# LightSwitch.net
KiCad netlist of a schematic drawn in EAGLE
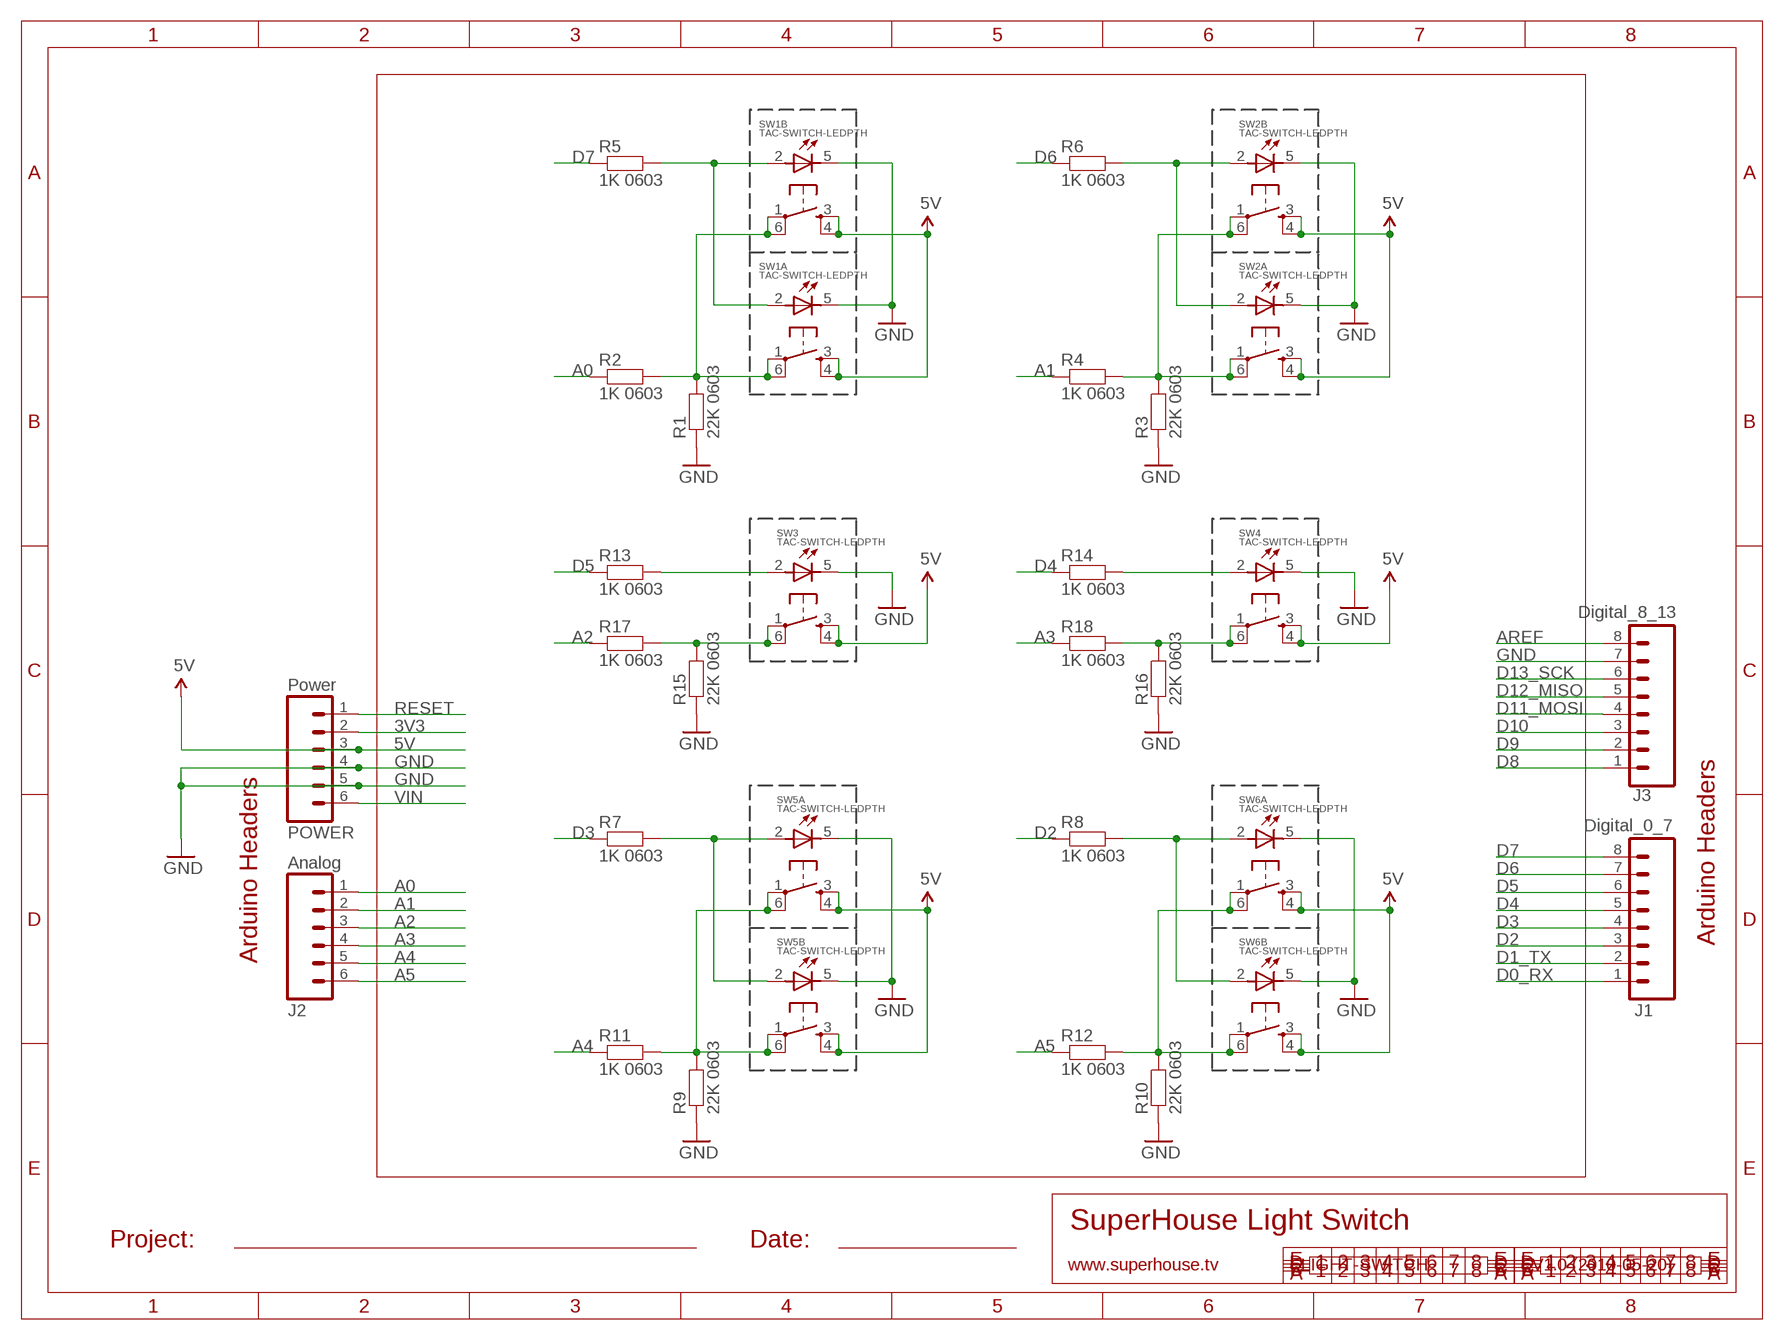
[diagram p0: schematic, sheet 1]

(export (version "E")
  (design (tool "Eeschema 10.0.6"))
  (components
    (comp (ref "J1")
      (value "Digital_0_7")
      (footprint "eagle-import:1X08")
      (libsource (lib "eagle-import") (part "M08"))
    )
    (comp (ref "J2")
      (value "Analog")
      (footprint "eagle-import:1X06")
      (libsource (lib "eagle-import") (part "M06SIP"))
    )
    (comp (ref "J3")
      (value "Digital_8_13")
      (footprint "eagle-import:1X08")
      (libsource (lib "eagle-import") (part "M08"))
    )
    (comp (ref "POWER")
      (value "Power")
      (footprint "eagle-import:1X06")
      (libsource (lib "eagle-import") (part "M06SIP"))
    )
    (comp (ref "R1")
      (value "22K 0603")
      (footprint "eagle-import:0603")
      (libsource (lib "eagle-import") (part "RESISTOR0603"))
    )
    (comp (ref "R2")
      (value "1K 0603")
      (footprint "eagle-import:0603")
      (libsource (lib "eagle-import") (part "RESISTOR0603"))
    )
    (comp (ref "R3")
      (value "22K 0603")
      (footprint "eagle-import:0603")
      (libsource (lib "eagle-import") (part "RESISTOR0603"))
    )
    (comp (ref "R4")
      (value "1K 0603")
      (footprint "eagle-import:0603")
      (libsource (lib "eagle-import") (part "RESISTOR0603"))
    )
    (comp (ref "R5")
      (value "1K 0603")
      (footprint "eagle-import:0603")
      (libsource (lib "eagle-import") (part "RESISTOR0603"))
    )
    (comp (ref "R6")
      (value "1K 0603")
      (footprint "eagle-import:0603")
      (libsource (lib "eagle-import") (part "RESISTOR0603"))
    )
    (comp (ref "R7")
      (value "1K 0603")
      (footprint "eagle-import:0603")
      (libsource (lib "eagle-import") (part "RESISTOR0603"))
    )
    (comp (ref "R8")
      (value "1K 0603")
      (footprint "eagle-import:0603")
      (libsource (lib "eagle-import") (part "RESISTOR0603"))
    )
    (comp (ref "R9")
      (value "22K 0603")
      (footprint "eagle-import:0603")
      (libsource (lib "eagle-import") (part "RESISTOR0603"))
    )
    (comp (ref "R10")
      (value "22K 0603")
      (footprint "eagle-import:0603")
      (libsource (lib "eagle-import") (part "RESISTOR0603"))
    )
    (comp (ref "R11")
      (value "1K 0603")
      (footprint "eagle-import:0603")
      (libsource (lib "eagle-import") (part "RESISTOR0603"))
    )
    (comp (ref "R12")
      (value "1K 0603")
      (footprint "eagle-import:0603")
      (libsource (lib "eagle-import") (part "RESISTOR0603"))
    )
    (comp (ref "R13")
      (value "1K 0603")
      (footprint "eagle-import:0603")
      (libsource (lib "eagle-import") (part "RESISTOR0603"))
    )
    (comp (ref "R14")
      (value "1K 0603")
      (footprint "eagle-import:0603")
      (libsource (lib "eagle-import") (part "RESISTOR0603"))
    )
    (comp (ref "R15")
      (value "22K 0603")
      (footprint "eagle-import:0603")
      (libsource (lib "eagle-import") (part "RESISTOR0603"))
    )
    (comp (ref "R16")
      (value "22K 0603")
      (footprint "eagle-import:0603")
      (libsource (lib "eagle-import") (part "RESISTOR0603"))
    )
    (comp (ref "R17")
      (value "1K 0603")
      (footprint "eagle-import:0603")
      (libsource (lib "eagle-import") (part "RESISTOR0603"))
    )
    (comp (ref "R18")
      (value "1K 0603")
      (footprint "eagle-import:0603")
      (libsource (lib "eagle-import") (part "RESISTOR0603"))
    )
    (comp (ref "SW1A")
      (value "TAC-SWITCH-LEDPTH")
      (footprint "eagle-import:TACTILE-LED")
      (libsource (lib "eagle-import") (part "TAC-SWITCH-LEDPTH"))
    )
    (comp (ref "SW1B")
      (value "TAC-SWITCH-LEDPTH")
      (footprint "eagle-import:TACTILE-LED")
      (libsource (lib "eagle-import") (part "TAC-SWITCH-LEDPTH"))
    )
    (comp (ref "SW2A")
      (value "TAC-SWITCH-LEDPTH")
      (footprint "eagle-import:TACTILE-LED")
      (libsource (lib "eagle-import") (part "TAC-SWITCH-LEDPTH"))
    )
    (comp (ref "SW2B")
      (value "TAC-SWITCH-LEDPTH")
      (footprint "eagle-import:TACTILE-LED")
      (libsource (lib "eagle-import") (part "TAC-SWITCH-LEDPTH"))
    )
    (comp (ref "SW3")
      (value "TAC-SWITCH-LEDPTH")
      (footprint "eagle-import:TACTILE-LED")
      (libsource (lib "eagle-import") (part "TAC-SWITCH-LEDPTH"))
    )
    (comp (ref "SW4")
      (value "TAC-SWITCH-LEDPTH")
      (footprint "eagle-import:TACTILE-LED")
      (libsource (lib "eagle-import") (part "TAC-SWITCH-LEDPTH"))
    )
    (comp (ref "SW5A")
      (value "TAC-SWITCH-LEDPTH")
      (footprint "eagle-import:TACTILE-LED")
      (libsource (lib "eagle-import") (part "TAC-SWITCH-LEDPTH"))
    )
    (comp (ref "SW5B")
      (value "TAC-SWITCH-LEDPTH")
      (footprint "eagle-import:TACTILE-LED")
      (libsource (lib "eagle-import") (part "TAC-SWITCH-LEDPTH"))
    )
    (comp (ref "SW6A")
      (value "TAC-SWITCH-LEDPTH")
      (footprint "eagle-import:TACTILE-LED")
      (libsource (lib "eagle-import") (part "TAC-SWITCH-LEDPTH"))
    )
    (comp (ref "SW6B")
      (value "TAC-SWITCH-LEDPTH")
      (footprint "eagle-import:TACTILE-LED")
      (libsource (lib "eagle-import") (part "TAC-SWITCH-LEDPTH"))
    )
  )
  (nets
    (net (code "1") (name "/3V3") (class "Default")
      (node (ref "POWER") (pin "2") (pinfunction "2_2") (pintype "passive"))
    )
    (net (code "2") (name "/A0") (class "Default")
      (node (ref "J2") (pin "1") (pinfunction "1_1") (pintype "passive"))
      (node (ref "R2") (pin "1") (pinfunction "1_1") (pintype "passive"))
    )
    (net (code "3") (name "/A1") (class "Default")
      (node (ref "J2") (pin "2") (pinfunction "2_2") (pintype "passive"))
      (node (ref "R4") (pin "1") (pinfunction "1_1") (pintype "passive"))
    )
    (net (code "4") (name "/A2") (class "Default")
      (node (ref "J2") (pin "3") (pinfunction "3_3") (pintype "passive"))
      (node (ref "R17") (pin "1") (pinfunction "1_1") (pintype "passive"))
    )
    (net (code "5") (name "/A3") (class "Default")
      (node (ref "J2") (pin "4") (pinfunction "4_4") (pintype "passive"))
      (node (ref "R18") (pin "1") (pinfunction "1_1") (pintype "passive"))
    )
    (net (code "6") (name "/A4") (class "Default")
      (node (ref "J2") (pin "5") (pinfunction "5_5") (pintype "passive"))
      (node (ref "R11") (pin "1") (pinfunction "1_1") (pintype "passive"))
    )
    (net (code "7") (name "/A5") (class "Default")
      (node (ref "J2") (pin "6") (pinfunction "6_6") (pintype "passive"))
      (node (ref "R12") (pin "1") (pinfunction "1_1") (pintype "passive"))
    )
    (net (code "8") (name "/AREF") (class "Default")
      (node (ref "J3") (pin "8") (pinfunction "8_8") (pintype "passive"))
    )
    (net (code "9") (name "/D0_RX") (class "Default")
      (node (ref "J1") (pin "1") (pinfunction "1_1") (pintype "passive"))
    )
    (net (code "10") (name "/D1_TX") (class "Default")
      (node (ref "J1") (pin "2") (pinfunction "2_2") (pintype "passive"))
    )
    (net (code "11") (name "/D2") (class "Default")
      (node (ref "J1") (pin "3") (pinfunction "3_3") (pintype "passive"))
      (node (ref "R8") (pin "1") (pinfunction "1_1") (pintype "passive"))
    )
    (net (code "12") (name "/D3") (class "Default")
      (node (ref "J1") (pin "4") (pinfunction "4_4") (pintype "passive"))
      (node (ref "R7") (pin "1") (pinfunction "1_1") (pintype "passive"))
    )
    (net (code "13") (name "/D4") (class "Default")
      (node (ref "J1") (pin "5") (pinfunction "5_5") (pintype "passive"))
      (node (ref "R14") (pin "1") (pinfunction "1_1") (pintype "passive"))
    )
    (net (code "14") (name "/D5") (class "Default")
      (node (ref "J1") (pin "6") (pinfunction "6_6") (pintype "passive"))
      (node (ref "R13") (pin "1") (pinfunction "1_1") (pintype "passive"))
    )
    (net (code "15") (name "/D6") (class "Default")
      (node (ref "J1") (pin "7") (pinfunction "7_7") (pintype "passive"))
      (node (ref "R6") (pin "1") (pinfunction "1_1") (pintype "passive"))
    )
    (net (code "16") (name "/D7") (class "Default")
      (node (ref "J1") (pin "8") (pinfunction "8_8") (pintype "passive"))
      (node (ref "R5") (pin "1") (pinfunction "1_1") (pintype "passive"))
    )
    (net (code "17") (name "/D8") (class "Default")
      (node (ref "J3") (pin "1") (pinfunction "1_1") (pintype "passive"))
    )
    (net (code "18") (name "/D9") (class "Default")
      (node (ref "J3") (pin "2") (pinfunction "2_2") (pintype "passive"))
    )
    (net (code "19") (name "/D10") (class "Default")
      (node (ref "J3") (pin "3") (pinfunction "3_3") (pintype "passive"))
    )
    (net (code "20") (name "/D11_MOSI") (class "Default")
      (node (ref "J3") (pin "4") (pinfunction "4_4") (pintype "passive"))
    )
    (net (code "21") (name "/D12_MISO") (class "Default")
      (node (ref "J3") (pin "5") (pinfunction "5_5") (pintype "passive"))
    )
    (net (code "22") (name "/D13_SCK") (class "Default")
      (node (ref "J3") (pin "6") (pinfunction "6_6") (pintype "passive"))
    )
    (net (code "23") (name "/RESET") (class "Default")
      (node (ref "POWER") (pin "1") (pinfunction "1_1") (pintype "passive"))
    )
    (net (code "24") (name "/VIN") (class "Default")
      (node (ref "POWER") (pin "6") (pinfunction "6_6") (pintype "passive"))
    )
    (net (code "25") (name "5V") (class "Default")
      (node (ref "POWER") (pin "3") (pinfunction "3_3") (pintype "passive"))
      (node (ref "SW1A") (pin "3") (pinfunction "3_3") (pintype "passive"))
      (node (ref "SW1A") (pin "4") (pinfunction "4_4") (pintype "passive"))
      (node (ref "SW1B") (pin "3") (pinfunction "3_3") (pintype "passive"))
      (node (ref "SW1B") (pin "4") (pinfunction "4_4") (pintype "passive"))
      (node (ref "SW2A") (pin "3") (pinfunction "3_3") (pintype "passive"))
      (node (ref "SW2A") (pin "4") (pinfunction "4_4") (pintype "passive"))
      (node (ref "SW2B") (pin "3") (pinfunction "3_3") (pintype "passive"))
      (node (ref "SW2B") (pin "4") (pinfunction "4_4") (pintype "passive"))
      (node (ref "SW3") (pin "3") (pinfunction "3_3") (pintype "passive"))
      (node (ref "SW3") (pin "4") (pinfunction "4_4") (pintype "passive"))
      (node (ref "SW4") (pin "3") (pinfunction "3_3") (pintype "passive"))
      (node (ref "SW4") (pin "4") (pinfunction "4_4") (pintype "passive"))
      (node (ref "SW5A") (pin "3") (pinfunction "3_3") (pintype "passive"))
      (node (ref "SW5A") (pin "4") (pinfunction "4_4") (pintype "passive"))
      (node (ref "SW5B") (pin "3") (pinfunction "3_3") (pintype "passive"))
      (node (ref "SW5B") (pin "4") (pinfunction "4_4") (pintype "passive"))
      (node (ref "SW6A") (pin "3") (pinfunction "3_3") (pintype "passive"))
      (node (ref "SW6A") (pin "4") (pinfunction "4_4") (pintype "passive"))
      (node (ref "SW6B") (pin "3") (pinfunction "3_3") (pintype "passive"))
      (node (ref "SW6B") (pin "4") (pinfunction "4_4") (pintype "passive"))
    )
    (net (code "26") (name "GND") (class "Default")
      (node (ref "J3") (pin "7") (pinfunction "7_7") (pintype "passive"))
      (node (ref "POWER") (pin "4") (pinfunction "4_4") (pintype "passive"))
      (node (ref "POWER") (pin "5") (pinfunction "5_5") (pintype "passive"))
      (node (ref "R1") (pin "1") (pinfunction "1_1") (pintype "passive"))
      (node (ref "R10") (pin "1") (pinfunction "1_1") (pintype "passive"))
      (node (ref "R15") (pin "1") (pinfunction "1_1") (pintype "passive"))
      (node (ref "R16") (pin "1") (pinfunction "1_1") (pintype "passive"))
      (node (ref "R3") (pin "1") (pinfunction "1_1") (pintype "passive"))
      (node (ref "R9") (pin "1") (pinfunction "1_1") (pintype "passive"))
      (node (ref "SW1A") (pin "5") (pinfunction "C_5") (pintype "passive"))
      (node (ref "SW1B") (pin "5") (pinfunction "C_5") (pintype "passive"))
      (node (ref "SW2A") (pin "5") (pinfunction "C_5") (pintype "passive"))
      (node (ref "SW2B") (pin "5") (pinfunction "C_5") (pintype "passive"))
      (node (ref "SW3") (pin "5") (pinfunction "C_5") (pintype "passive"))
      (node (ref "SW4") (pin "5") (pinfunction "C_5") (pintype "passive"))
      (node (ref "SW5A") (pin "5") (pinfunction "C_5") (pintype "passive"))
      (node (ref "SW5B") (pin "5") (pinfunction "C_5") (pintype "passive"))
      (node (ref "SW6A") (pin "5") (pinfunction "C_5") (pintype "passive"))
      (node (ref "SW6B") (pin "5") (pinfunction "C_5") (pintype "passive"))
    )
    (net (code "27") (name "Net-(R1-Pad2)") (class "Default")
      (node (ref "R1") (pin "2") (pinfunction "2_2") (pintype "passive"))
      (node (ref "R2") (pin "2") (pinfunction "2_2") (pintype "passive"))
      (node (ref "SW1A") (pin "1") (pinfunction "1_1") (pintype "passive"))
      (node (ref "SW1A") (pin "6") (pinfunction "6_6") (pintype "passive"))
      (node (ref "SW1B") (pin "1") (pinfunction "1_1") (pintype "passive"))
      (node (ref "SW1B") (pin "6") (pinfunction "6_6") (pintype "passive"))
    )
    (net (code "28") (name "Net-(R3-Pad2)") (class "Default")
      (node (ref "R3") (pin "2") (pinfunction "2_2") (pintype "passive"))
      (node (ref "R4") (pin "2") (pinfunction "2_2") (pintype "passive"))
      (node (ref "SW2A") (pin "1") (pinfunction "1_1") (pintype "passive"))
      (node (ref "SW2A") (pin "6") (pinfunction "6_6") (pintype "passive"))
      (node (ref "SW2B") (pin "1") (pinfunction "1_1") (pintype "passive"))
      (node (ref "SW2B") (pin "6") (pinfunction "6_6") (pintype "passive"))
    )
    (net (code "29") (name "Net-(R10-Pad2)") (class "Default")
      (node (ref "R10") (pin "2") (pinfunction "2_2") (pintype "passive"))
      (node (ref "R12") (pin "2") (pinfunction "2_2") (pintype "passive"))
      (node (ref "SW6A") (pin "1") (pinfunction "1_1") (pintype "passive"))
      (node (ref "SW6A") (pin "6") (pinfunction "6_6") (pintype "passive"))
      (node (ref "SW6B") (pin "1") (pinfunction "1_1") (pintype "passive"))
      (node (ref "SW6B") (pin "6") (pinfunction "6_6") (pintype "passive"))
    )
    (net (code "30") (name "Net-(R11-Pad2)") (class "Default")
      (node (ref "R11") (pin "2") (pinfunction "2_2") (pintype "passive"))
      (node (ref "R9") (pin "2") (pinfunction "2_2") (pintype "passive"))
      (node (ref "SW5A") (pin "1") (pinfunction "1_1") (pintype "passive"))
      (node (ref "SW5A") (pin "6") (pinfunction "6_6") (pintype "passive"))
      (node (ref "SW5B") (pin "1") (pinfunction "1_1") (pintype "passive"))
      (node (ref "SW5B") (pin "6") (pinfunction "6_6") (pintype "passive"))
    )
    (net (code "31") (name "Net-(R15-Pad2)") (class "Default")
      (node (ref "R15") (pin "2") (pinfunction "2_2") (pintype "passive"))
      (node (ref "R17") (pin "2") (pinfunction "2_2") (pintype "passive"))
      (node (ref "SW3") (pin "1") (pinfunction "1_1") (pintype "passive"))
      (node (ref "SW3") (pin "6") (pinfunction "6_6") (pintype "passive"))
    )
    (net (code "32") (name "Net-(R16-Pad2)") (class "Default")
      (node (ref "R16") (pin "2") (pinfunction "2_2") (pintype "passive"))
      (node (ref "R18") (pin "2") (pinfunction "2_2") (pintype "passive"))
      (node (ref "SW4") (pin "1") (pinfunction "1_1") (pintype "passive"))
      (node (ref "SW4") (pin "6") (pinfunction "6_6") (pintype "passive"))
    )
    (net (code "33") (name "Net-(SW1A-A)") (class "Default")
      (node (ref "R5") (pin "2") (pinfunction "2_2") (pintype "passive"))
      (node (ref "SW1A") (pin "2") (pinfunction "A_2") (pintype "passive"))
      (node (ref "SW1B") (pin "2") (pinfunction "A_2") (pintype "passive"))
    )
    (net (code "34") (name "Net-(SW2A-A)") (class "Default")
      (node (ref "R6") (pin "2") (pinfunction "2_2") (pintype "passive"))
      (node (ref "SW2A") (pin "2") (pinfunction "A_2") (pintype "passive"))
      (node (ref "SW2B") (pin "2") (pinfunction "A_2") (pintype "passive"))
    )
    (net (code "35") (name "Net-(SW3-A)") (class "Default")
      (node (ref "R13") (pin "2") (pinfunction "2_2") (pintype "passive"))
      (node (ref "SW3") (pin "2") (pinfunction "A_2") (pintype "passive"))
    )
    (net (code "36") (name "Net-(SW4-A)") (class "Default")
      (node (ref "R14") (pin "2") (pinfunction "2_2") (pintype "passive"))
      (node (ref "SW4") (pin "2") (pinfunction "A_2") (pintype "passive"))
    )
    (net (code "37") (name "Net-(SW5A-A)") (class "Default")
      (node (ref "R7") (pin "2") (pinfunction "2_2") (pintype "passive"))
      (node (ref "SW5A") (pin "2") (pinfunction "A_2") (pintype "passive"))
      (node (ref "SW5B") (pin "2") (pinfunction "A_2") (pintype "passive"))
    )
    (net (code "38") (name "Net-(SW6A-A)") (class "Default")
      (node (ref "R8") (pin "2") (pinfunction "2_2") (pintype "passive"))
      (node (ref "SW6A") (pin "2") (pinfunction "A_2") (pintype "passive"))
      (node (ref "SW6B") (pin "2") (pinfunction "A_2") (pintype "passive"))
    )
  )
)
